# STM32H750IBK6.net
KiCad netlist of a schematic drawn in Altium Designer
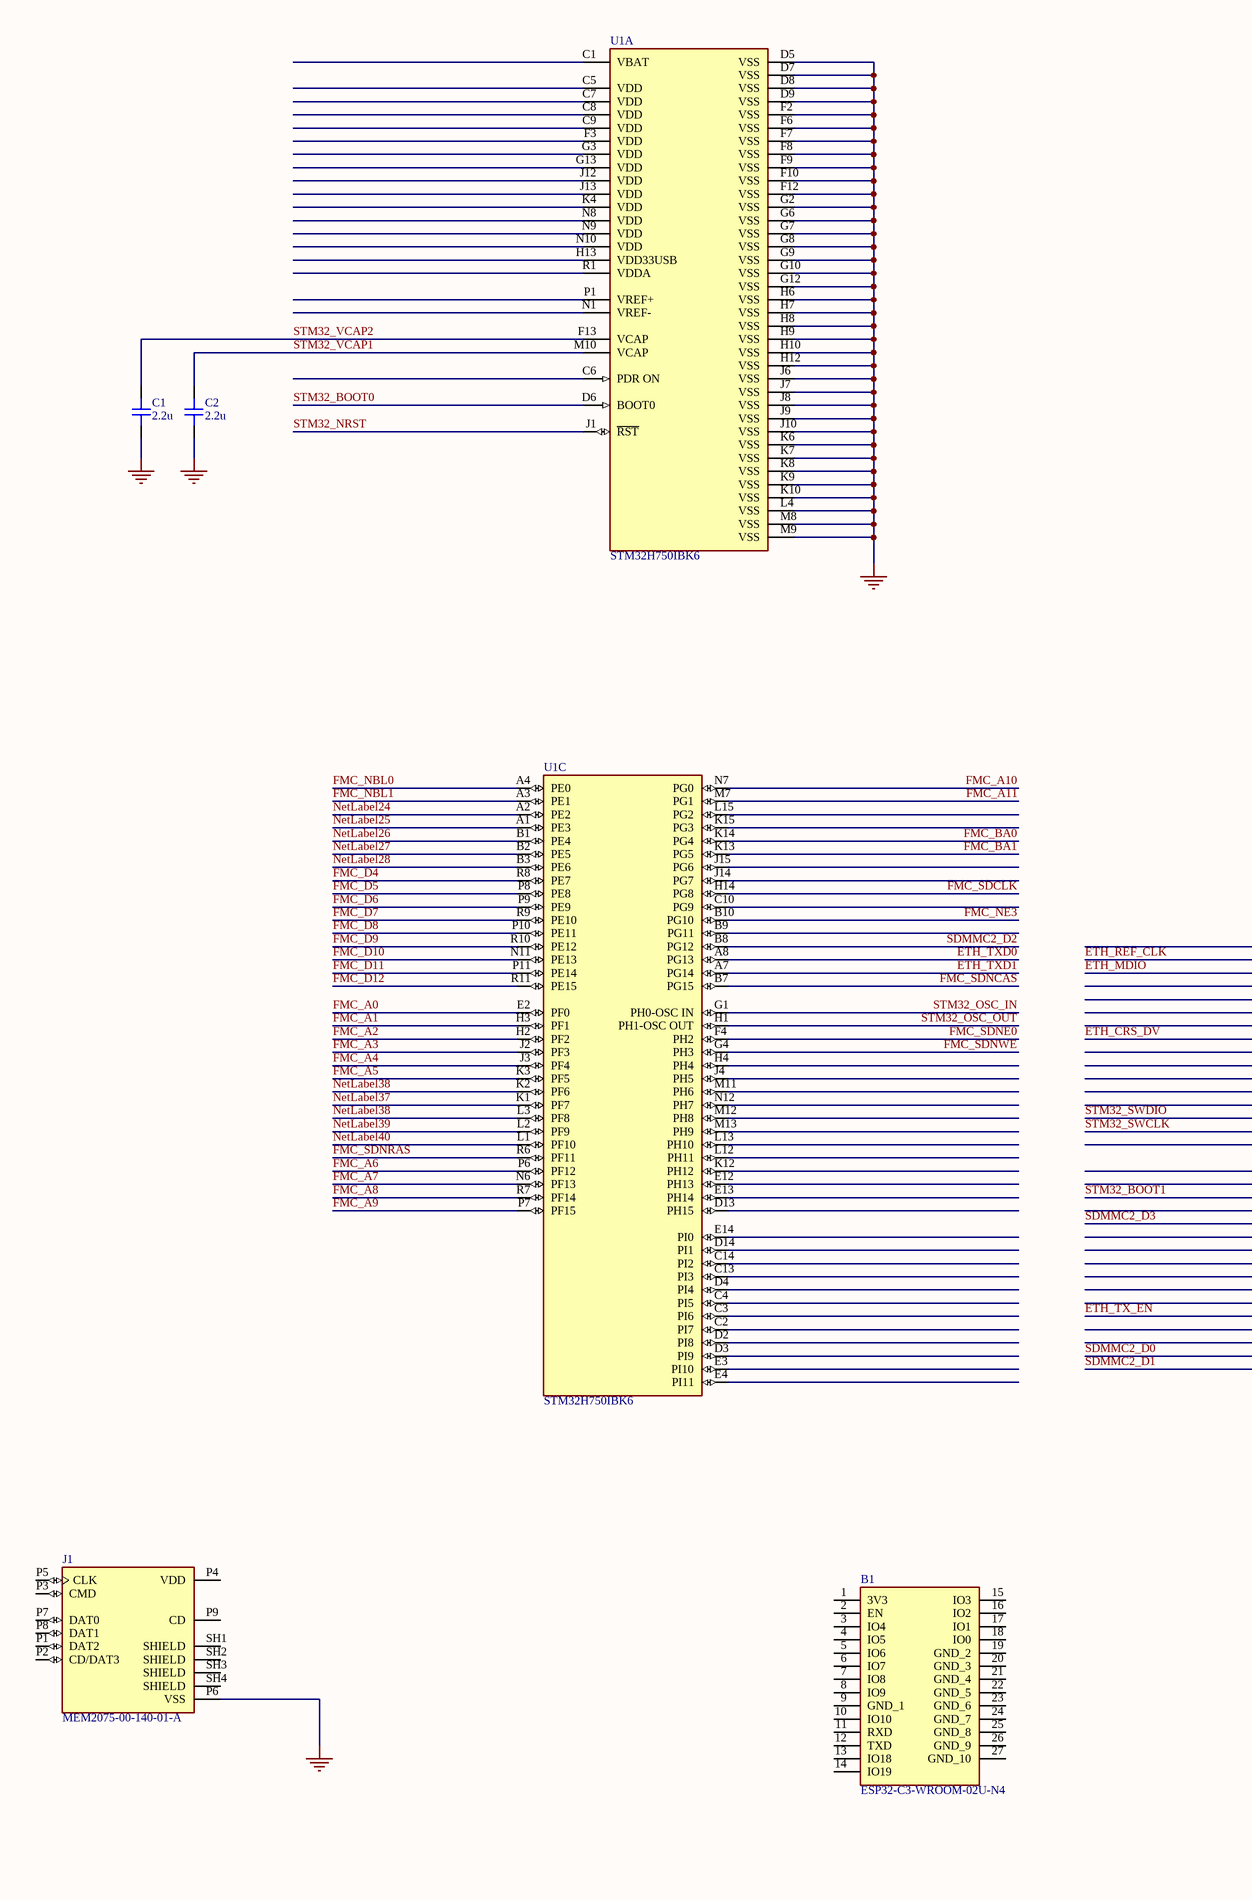
[diagram p0: STM32H750IBK6.SchDoc, left]
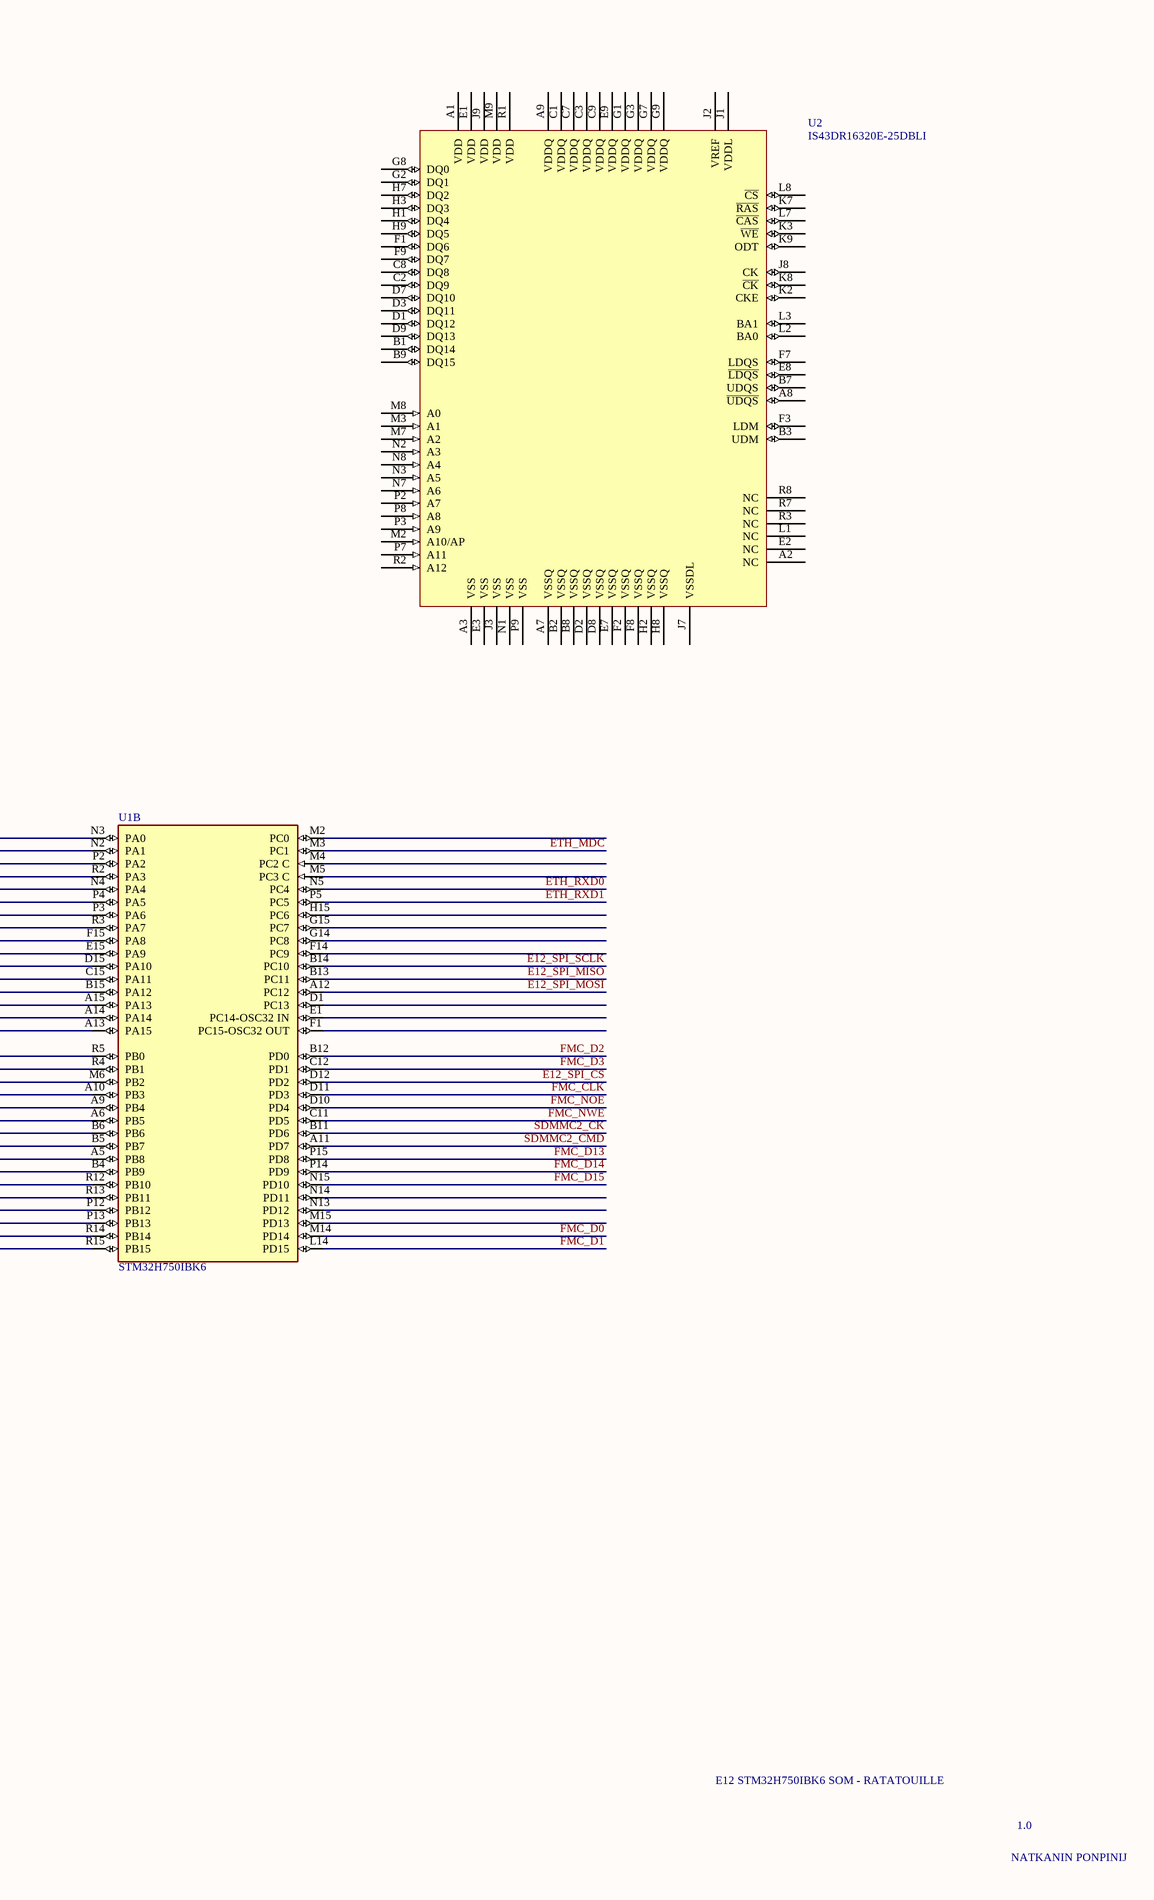
[diagram p1: STM32H750IBK6.SchDoc, right]

(export (version "E")
  (design (tool "Eeschema 10.0.6"))
  (components
    (comp (ref "B1")
      (value "ESP32-C3-WROOM-02U-N4")
      (footprint "ESP32C3WROOM02UN4")
      (description "Multiprotocol Modules SMD module, ESP32-C3, 4MB SPI flash, IPEX antenna, -40 C +85 C")
      (fields (field (name "MOUSER PART NUMBER") "356-ESP32C3WROM02UN4"))
      (libsource (lib "ESP32-C3-WROOM-02U-N4") (part "ESP32-C3-WROOM-02U-N4"))
    )
    (comp (ref "C1")
      (value "2.2u")
      (footprint "CAP_0402")
      (description "Capacitor SMD 0402 10V")
      (libsource (lib "Schematic-Lib-PhilsLab") (part "CAP_0402_10V"))
    )
    (comp (ref "C2")
      (value "2.2u")
      (footprint "CAP_0402")
      (description "Capacitor SMD 0402 10V")
      (libsource (lib "Schematic-Lib-PhilsLab") (part "CAP_0402_10V"))
    )
    (comp (ref "J1")
      (value "MEM2075-00-140-01-A")
      (footprint "GCT_MEM2075-00-140-01-A")
      (description "Micro SD Memory Card Connector, 1.4mm Profile SMT, Push-Push, with Normally open Switch")
      (libsource (lib "MEM2075-00-140-01-A") (part "MEM2075-00-140-01-A"))
    )
    (comp (ref "U1")
      (value "STM32H750IBK6")
      (footprint "FP-UFBGA176+25-A0E7-MFG")
      (description "IC MCU 32BIT 128KB FLASH 176UBGA")
      (fields
        (field (name "MANUFACTURER") "STMicroelectronics")
        (field (name "OCTOPART") "https://octopart.com/stm32h750ibk6-stmicroelectronics-94048546")
      )
      (libsource (lib "Altium Content Vault") (part "47281e30408f4b5e06a14b8d1ab2598"))
    )
    (comp (ref "U2")
      (value "IS43DR16320E-25DBLI")
      (footprint "BGA84C80P9X15_800X1250X120")
      (libsource (lib "E12WorkSpace") (part "IS43DR16320E-25DBLI-Symbol-1"))
    )
  )
  (nets
    (net (code "1") (name "/E12_SPI_CS") (class "Default")
      (node (ref "U1") (pin "D12") (pinfunction "PD2_D12") (pintype "bidirectional"))
    )
    (net (code "2") (name "/E12_SPI_MISO") (class "Default")
      (node (ref "U1") (pin "B13") (pinfunction "PC11_B13") (pintype "bidirectional"))
    )
    (net (code "3") (name "/E12_SPI_MOSI") (class "Default")
      (node (ref "U1") (pin "A12") (pinfunction "PC12_A12") (pintype "bidirectional"))
    )
    (net (code "4") (name "/E12_SPI_SCLK") (class "Default")
      (node (ref "U1") (pin "B14") (pinfunction "PC10_B14") (pintype "bidirectional"))
    )
    (net (code "5") (name "/ETH_CRS_DV") (class "Default")
      (node (ref "U1") (pin "R3") (pinfunction "PA7_R3") (pintype "bidirectional"))
    )
    (net (code "6") (name "/ETH_MDC") (class "Default")
      (node (ref "U1") (pin "M3") (pinfunction "PC1_M3") (pintype "bidirectional"))
    )
    (net (code "7") (name "/ETH_MDIO") (class "Default")
      (node (ref "U1") (pin "P2") (pinfunction "PA2_P2") (pintype "bidirectional"))
    )
    (net (code "8") (name "/ETH_REF_CLK") (class "Default")
      (node (ref "U1") (pin "N2") (pinfunction "PA1_N2") (pintype "bidirectional"))
    )
    (net (code "9") (name "/ETH_RXD0") (class "Default")
      (node (ref "U1") (pin "N5") (pinfunction "PC4_N5") (pintype "bidirectional"))
    )
    (net (code "10") (name "/ETH_RXD1") (class "Default")
      (node (ref "U1") (pin "P5") (pinfunction "PC5_P5") (pintype "bidirectional"))
    )
    (net (code "11") (name "/ETH_TXD0") (class "Default")
      (node (ref "U1") (pin "A8") (pinfunction "PG13_A8") (pintype "bidirectional"))
    )
    (net (code "12") (name "/ETH_TXD1") (class "Default")
      (node (ref "U1") (pin "A7") (pinfunction "PG14_A7") (pintype "bidirectional"))
    )
    (net (code "13") (name "/ETH_TX_EN") (class "Default")
      (node (ref "U1") (pin "R13") (pinfunction "PB11_R13") (pintype "bidirectional"))
    )
    (net (code "14") (name "/FMC_A0") (class "Default")
      (node (ref "U1") (pin "E2") (pinfunction "PF0_E2") (pintype "bidirectional"))
    )
    (net (code "15") (name "/FMC_A1") (class "Default")
      (node (ref "U1") (pin "H3") (pinfunction "PF1_H3") (pintype "bidirectional"))
    )
    (net (code "16") (name "/FMC_A2") (class "Default")
      (node (ref "U1") (pin "H2") (pinfunction "PF2_H2") (pintype "bidirectional"))
    )
    (net (code "17") (name "/FMC_A3") (class "Default")
      (node (ref "U1") (pin "J2") (pinfunction "PF3_J2") (pintype "bidirectional"))
    )
    (net (code "18") (name "/FMC_A4") (class "Default")
      (node (ref "U1") (pin "J3") (pinfunction "PF4_J3") (pintype "bidirectional"))
    )
    (net (code "19") (name "/FMC_A5") (class "Default")
      (node (ref "U1") (pin "K3") (pinfunction "PF5_K3") (pintype "bidirectional"))
    )
    (net (code "20") (name "/FMC_A6") (class "Default")
      (node (ref "U1") (pin "P6") (pinfunction "PF12_P6") (pintype "bidirectional"))
    )
    (net (code "21") (name "/FMC_A7") (class "Default")
      (node (ref "U1") (pin "N6") (pinfunction "PF13_N6") (pintype "bidirectional"))
    )
    (net (code "22") (name "/FMC_A8") (class "Default")
      (node (ref "U1") (pin "R7") (pinfunction "PF14_R7") (pintype "bidirectional"))
    )
    (net (code "23") (name "/FMC_A9") (class "Default")
      (node (ref "U1") (pin "P7") (pinfunction "PF15_P7") (pintype "bidirectional"))
    )
    (net (code "24") (name "/FMC_A10") (class "Default")
      (node (ref "U1") (pin "N7") (pinfunction "PG0_N7") (pintype "bidirectional"))
    )
    (net (code "25") (name "/FMC_A11") (class "Default")
      (node (ref "U1") (pin "M7") (pinfunction "PG1_M7") (pintype "bidirectional"))
    )
    (net (code "26") (name "/FMC_BA0") (class "Default")
      (node (ref "U1") (pin "K14") (pinfunction "PG4_K14") (pintype "bidirectional"))
    )
    (net (code "27") (name "/FMC_BA1") (class "Default")
      (node (ref "U1") (pin "K13") (pinfunction "PG5_K13") (pintype "bidirectional"))
    )
    (net (code "28") (name "/FMC_CLK") (class "Default")
      (node (ref "U1") (pin "D11") (pinfunction "PD3_D11") (pintype "bidirectional"))
    )
    (net (code "29") (name "/FMC_D0") (class "Default")
      (node (ref "U1") (pin "M14") (pinfunction "PD14_M14") (pintype "bidirectional"))
    )
    (net (code "30") (name "/FMC_D1") (class "Default")
      (node (ref "U1") (pin "L14") (pinfunction "PD15_L14") (pintype "bidirectional"))
    )
    (net (code "31") (name "/FMC_D2") (class "Default")
      (node (ref "U1") (pin "B12") (pinfunction "PD0_B12") (pintype "bidirectional"))
    )
    (net (code "32") (name "/FMC_D3") (class "Default")
      (node (ref "U1") (pin "C12") (pinfunction "PD1_C12") (pintype "bidirectional"))
    )
    (net (code "33") (name "/FMC_D4") (class "Default")
      (node (ref "U1") (pin "R8") (pinfunction "PE7_R8") (pintype "bidirectional"))
    )
    (net (code "34") (name "/FMC_D5") (class "Default")
      (node (ref "U1") (pin "P8") (pinfunction "PE8_P8") (pintype "bidirectional"))
    )
    (net (code "35") (name "/FMC_D6") (class "Default")
      (node (ref "U1") (pin "P9") (pinfunction "PE9_P9") (pintype "bidirectional"))
    )
    (net (code "36") (name "/FMC_D7") (class "Default")
      (node (ref "U1") (pin "R9") (pinfunction "PE10_R9") (pintype "bidirectional"))
    )
    (net (code "37") (name "/FMC_D8") (class "Default")
      (node (ref "U1") (pin "P10") (pinfunction "PE11_P10") (pintype "bidirectional"))
    )
    (net (code "38") (name "/FMC_D9") (class "Default")
      (node (ref "U1") (pin "R10") (pinfunction "PE12_R10") (pintype "bidirectional"))
    )
    (net (code "39") (name "/FMC_D10") (class "Default")
      (node (ref "U1") (pin "N11") (pinfunction "PE13_N11") (pintype "bidirectional"))
    )
    (net (code "40") (name "/FMC_D11") (class "Default")
      (node (ref "U1") (pin "P11") (pinfunction "PE14_P11") (pintype "bidirectional"))
    )
    (net (code "41") (name "/FMC_D12") (class "Default")
      (node (ref "U1") (pin "R11") (pinfunction "PE15_R11") (pintype "bidirectional"))
    )
    (net (code "42") (name "/FMC_D13") (class "Default")
      (node (ref "U1") (pin "P15") (pinfunction "PD8_P15") (pintype "bidirectional"))
    )
    (net (code "43") (name "/FMC_D14") (class "Default")
      (node (ref "U1") (pin "P14") (pinfunction "PD9_P14") (pintype "bidirectional"))
    )
    (net (code "44") (name "/FMC_D15") (class "Default")
      (node (ref "U1") (pin "N15") (pinfunction "PD10_N15") (pintype "bidirectional"))
    )
    (net (code "45") (name "/FMC_NBL0") (class "Default")
      (node (ref "U1") (pin "A4") (pinfunction "PE0_A4") (pintype "bidirectional"))
    )
    (net (code "46") (name "/FMC_NBL1") (class "Default")
      (node (ref "U1") (pin "A3") (pinfunction "PE1_A3") (pintype "bidirectional"))
    )
    (net (code "47") (name "/FMC_NE3") (class "Default")
      (node (ref "U1") (pin "B10") (pinfunction "PG10_B10") (pintype "bidirectional"))
    )
    (net (code "48") (name "/FMC_NOE") (class "Default")
      (node (ref "U1") (pin "D10") (pinfunction "PD4_D10") (pintype "bidirectional"))
    )
    (net (code "49") (name "/FMC_NWE") (class "Default")
      (node (ref "U1") (pin "C11") (pinfunction "PD5_C11") (pintype "bidirectional"))
    )
    (net (code "50") (name "/FMC_SDCLK") (class "Default")
      (node (ref "U1") (pin "H14") (pinfunction "PG8_H14") (pintype "bidirectional"))
    )
    (net (code "51") (name "/FMC_SDNCAS") (class "Default")
      (node (ref "U1") (pin "B7") (pinfunction "PG15_B7") (pintype "bidirectional"))
    )
    (net (code "52") (name "/FMC_SDNE0") (class "Default")
      (node (ref "U1") (pin "F4") (pinfunction "PH2_F4") (pintype "bidirectional"))
    )
    (net (code "53") (name "/FMC_SDNRAS") (class "Default")
      (node (ref "U1") (pin "R6") (pinfunction "PF11_R6") (pintype "bidirectional"))
    )
    (net (code "54") (name "/FMC_SDNWE") (class "Default")
      (node (ref "U1") (pin "G4") (pinfunction "PH3_G4") (pintype "bidirectional"))
    )
    (net (code "55") (name "/NetLabel24") (class "Default")
      (node (ref "U1") (pin "A2") (pinfunction "PE2_A2") (pintype "bidirectional"))
    )
    (net (code "56") (name "/NetLabel25") (class "Default")
      (node (ref "U1") (pin "A1") (pinfunction "PE3_A1") (pintype "bidirectional"))
    )
    (net (code "57") (name "/NetLabel26") (class "Default")
      (node (ref "U1") (pin "B1") (pinfunction "PE4_B1") (pintype "bidirectional"))
    )
    (net (code "58") (name "/NetLabel27") (class "Default")
      (node (ref "U1") (pin "B2") (pinfunction "PE5_B2") (pintype "bidirectional"))
    )
    (net (code "59") (name "/NetLabel28") (class "Default")
      (node (ref "U1") (pin "B3") (pinfunction "PE6_B3") (pintype "bidirectional"))
    )
    (net (code "60") (name "/NetLabel37") (class "Default")
      (node (ref "U1") (pin "K1") (pinfunction "PF7_K1") (pintype "bidirectional"))
    )
    (net (code "61") (name "/NetLabel38") (class "Default")
      (node (ref "U1") (pin "K2") (pinfunction "PF6_K2") (pintype "bidirectional"))
      (node (ref "U1") (pin "L3") (pinfunction "PF8_L3") (pintype "bidirectional"))
    )
    (net (code "62") (name "/NetLabel39") (class "Default")
      (node (ref "U1") (pin "L2") (pinfunction "PF9_L2") (pintype "bidirectional"))
    )
    (net (code "63") (name "/NetLabel40") (class "Default")
      (node (ref "U1") (pin "L1") (pinfunction "PF10_L1") (pintype "bidirectional"))
    )
    (net (code "64") (name "/SDMMC2_CK") (class "Default")
      (node (ref "U1") (pin "B11") (pinfunction "PD6_B11") (pintype "bidirectional"))
    )
    (net (code "65") (name "/SDMMC2_CMD") (class "Default")
      (node (ref "U1") (pin "A11") (pinfunction "PD7_A11") (pintype "bidirectional"))
    )
    (net (code "66") (name "/SDMMC2_D0") (class "Default")
      (node (ref "U1") (pin "R14") (pinfunction "PB14_R14") (pintype "bidirectional"))
    )
    (net (code "67") (name "/SDMMC2_D1") (class "Default")
      (node (ref "U1") (pin "R15") (pinfunction "PB15_R15") (pintype "bidirectional"))
    )
    (net (code "68") (name "/SDMMC2_D2") (class "Default")
      (node (ref "U1") (pin "B8") (pinfunction "PG12_B8") (pintype "bidirectional"))
    )
    (net (code "69") (name "/SDMMC2_D3") (class "Default")
      (node (ref "U1") (pin "A9") (pinfunction "PB4_A9") (pintype "bidirectional"))
    )
    (net (code "70") (name "/STM32_BOOT0") (class "Default")
      (node (ref "U1") (pin "D6") (pinfunction "BOOT0_D6") (pintype "input"))
    )
    (net (code "71") (name "/STM32_BOOT1") (class "Default")
      (node (ref "U1") (pin "M6") (pinfunction "PB2_M6") (pintype "bidirectional"))
    )
    (net (code "72") (name "/STM32_NRST") (class "Default")
      (node (ref "U1") (pin "J1") (pinfunction "~{RST}_J1") (pintype "bidirectional"))
    )
    (net (code "73") (name "/STM32_OSC_IN") (class "Default")
      (node (ref "U1") (pin "G1") (pinfunction "PH0-OSC_IN_G1") (pintype "bidirectional"))
    )
    (net (code "74") (name "/STM32_OSC_OUT") (class "Default")
      (node (ref "U1") (pin "H1") (pinfunction "PH1-OSC_OUT_H1") (pintype "bidirectional"))
    )
    (net (code "75") (name "/STM32_SWCLK") (class "Default")
      (node (ref "U1") (pin "A14") (pinfunction "PA14_A14") (pintype "bidirectional"))
    )
    (net (code "76") (name "/STM32_SWDIO") (class "Default")
      (node (ref "U1") (pin "A15") (pinfunction "PA13_A15") (pintype "bidirectional"))
    )
    (net (code "77") (name "/STM32_VCAP1") (class "Default")
      (node (ref "C2") (pin "2") (pinfunction "2_2") (pintype "passive"))
      (node (ref "U1") (pin "M10") (pinfunction "VCAP_M10") (pintype "power_in"))
    )
    (net (code "78") (name "/STM32_VCAP2") (class "Default")
      (node (ref "C1") (pin "2") (pinfunction "2_2") (pintype "passive"))
      (node (ref "U1") (pin "F13") (pinfunction "VCAP_F13") (pintype "power_in"))
    )
    (net (code "79") (name "GND") (class "Default")
      (node (ref "C1") (pin "1") (pinfunction "1_1") (pintype "passive"))
      (node (ref "C2") (pin "1") (pinfunction "1_1") (pintype "passive"))
      (node (ref "J1") (pin "P6") (pinfunction "VSS_P6") (pintype "power_in"))
      (node (ref "U1") (pin "D5") (pinfunction "VSS_D5") (pintype "power_in"))
      (node (ref "U1") (pin "D7") (pinfunction "VSS_D7") (pintype "power_in"))
      (node (ref "U1") (pin "D8") (pinfunction "VSS_D8") (pintype "power_in"))
      (node (ref "U1") (pin "D9") (pinfunction "VSS_D9") (pintype "power_in"))
      (node (ref "U1") (pin "F10") (pinfunction "VSS_F10") (pintype "power_in"))
      (node (ref "U1") (pin "F12") (pinfunction "VSS_F12") (pintype "power_in"))
      (node (ref "U1") (pin "F2") (pinfunction "VSS_F2") (pintype "power_in"))
      (node (ref "U1") (pin "F6") (pinfunction "VSS_F6") (pintype "power_in"))
      (node (ref "U1") (pin "F7") (pinfunction "VSS_F7") (pintype "power_in"))
      (node (ref "U1") (pin "F8") (pinfunction "VSS_F8") (pintype "power_in"))
      (node (ref "U1") (pin "F9") (pinfunction "VSS_F9") (pintype "power_in"))
      (node (ref "U1") (pin "G10") (pinfunction "VSS_G10") (pintype "power_in"))
      (node (ref "U1") (pin "G12") (pinfunction "VSS_G12") (pintype "power_in"))
      (node (ref "U1") (pin "G2") (pinfunction "VSS_G2") (pintype "power_in"))
      (node (ref "U1") (pin "G6") (pinfunction "VSS_G6") (pintype "power_in"))
      (node (ref "U1") (pin "G7") (pinfunction "VSS_G7") (pintype "power_in"))
      (node (ref "U1") (pin "G8") (pinfunction "VSS_G8") (pintype "power_in"))
      (node (ref "U1") (pin "G9") (pinfunction "VSS_G9") (pintype "power_in"))
      (node (ref "U1") (pin "H10") (pinfunction "VSS_H10") (pintype "power_in"))
      (node (ref "U1") (pin "H12") (pinfunction "VSS_H12") (pintype "power_in"))
      (node (ref "U1") (pin "H6") (pinfunction "VSS_H6") (pintype "power_in"))
      (node (ref "U1") (pin "H7") (pinfunction "VSS_H7") (pintype "power_in"))
      (node (ref "U1") (pin "H8") (pinfunction "VSS_H8") (pintype "power_in"))
      (node (ref "U1") (pin "H9") (pinfunction "VSS_H9") (pintype "power_in"))
      (node (ref "U1") (pin "J10") (pinfunction "VSS_J10") (pintype "power_in"))
      (node (ref "U1") (pin "J6") (pinfunction "VSS_J6") (pintype "power_in"))
      (node (ref "U1") (pin "J7") (pinfunction "VSS_J7") (pintype "power_in"))
      (node (ref "U1") (pin "J8") (pinfunction "VSS_J8") (pintype "power_in"))
      (node (ref "U1") (pin "J9") (pinfunction "VSS_J9") (pintype "power_in"))
      (node (ref "U1") (pin "K10") (pinfunction "VSS_K10") (pintype "power_in"))
      (node (ref "U1") (pin "K6") (pinfunction "VSS_K6") (pintype "power_in"))
      (node (ref "U1") (pin "K7") (pinfunction "VSS_K7") (pintype "power_in"))
      (node (ref "U1") (pin "K8") (pinfunction "VSS_K8") (pintype "power_in"))
      (node (ref "U1") (pin "K9") (pinfunction "VSS_K9") (pintype "power_in"))
      (node (ref "U1") (pin "L4") (pinfunction "VSS_L4") (pintype "power_in"))
      (node (ref "U1") (pin "M8") (pinfunction "VSS_M8") (pintype "power_in"))
      (node (ref "U1") (pin "M9") (pinfunction "VSS_M9") (pintype "power_in"))
    )
    (net (code "80") (name "unconnected-(B1-3V3-Pad1)") (class "Default")
      (node (ref "B1") (pin "1") (pinfunction "3V3_1") (pintype "passive"))
    )
    (net (code "81") (name "unconnected-(B1-EN-Pad2)") (class "Default")
      (node (ref "B1") (pin "2") (pinfunction "EN_2") (pintype "passive"))
    )
    (net (code "82") (name "unconnected-(B1-GND_1-Pad9)") (class "Default")
      (node (ref "B1") (pin "9") (pinfunction "GND_1_9") (pintype "passive"))
    )
    (net (code "83") (name "unconnected-(B1-GND_2-Pad19)") (class "Default")
      (node (ref "B1") (pin "19") (pinfunction "GND_2_19") (pintype "passive"))
    )
    (net (code "84") (name "unconnected-(B1-GND_3-Pad20)") (class "Default")
      (node (ref "B1") (pin "20") (pinfunction "GND_3_20") (pintype "passive"))
    )
    (net (code "85") (name "unconnected-(B1-GND_4-Pad21)") (class "Default")
      (node (ref "B1") (pin "21") (pinfunction "GND_4_21") (pintype "passive"))
    )
    (net (code "86") (name "unconnected-(B1-GND_5-Pad22)") (class "Default")
      (node (ref "B1") (pin "22") (pinfunction "GND_5_22") (pintype "passive"))
    )
    (net (code "87") (name "unconnected-(B1-GND_6-Pad23)") (class "Default")
      (node (ref "B1") (pin "23") (pinfunction "GND_6_23") (pintype "passive"))
    )
    (net (code "88") (name "unconnected-(B1-GND_7-Pad24)") (class "Default")
      (node (ref "B1") (pin "24") (pinfunction "GND_7_24") (pintype "passive"))
    )
    (net (code "89") (name "unconnected-(B1-GND_8-Pad25)") (class "Default")
      (node (ref "B1") (pin "25") (pinfunction "GND_8_25") (pintype "passive"))
    )
    (net (code "90") (name "unconnected-(B1-GND_9-Pad26)") (class "Default")
      (node (ref "B1") (pin "26") (pinfunction "GND_9_26") (pintype "passive"))
    )
    (net (code "91") (name "unconnected-(B1-GND_10-Pad27)") (class "Default")
      (node (ref "B1") (pin "27") (pinfunction "GND_10_27") (pintype "passive"))
    )
    (net (code "92") (name "unconnected-(B1-IO0-Pad18)") (class "Default")
      (node (ref "B1") (pin "18") (pinfunction "IO0_18") (pintype "passive"))
    )
    (net (code "93") (name "unconnected-(B1-IO1-Pad17)") (class "Default")
      (node (ref "B1") (pin "17") (pinfunction "IO1_17") (pintype "passive"))
    )
    (net (code "94") (name "unconnected-(B1-IO2-Pad16)") (class "Default")
      (node (ref "B1") (pin "16") (pinfunction "IO2_16") (pintype "passive"))
    )
    (net (code "95") (name "unconnected-(B1-IO3-Pad15)") (class "Default")
      (node (ref "B1") (pin "15") (pinfunction "IO3_15") (pintype "passive"))
    )
    (net (code "96") (name "unconnected-(B1-IO4-Pad3)") (class "Default")
      (node (ref "B1") (pin "3") (pinfunction "IO4_3") (pintype "passive"))
    )
    (net (code "97") (name "unconnected-(B1-IO5-Pad4)") (class "Default")
      (node (ref "B1") (pin "4") (pinfunction "IO5_4") (pintype "passive"))
    )
    (net (code "98") (name "unconnected-(B1-IO6-Pad5)") (class "Default")
      (node (ref "B1") (pin "5") (pinfunction "IO6_5") (pintype "passive"))
    )
    (net (code "99") (name "unconnected-(B1-IO7-Pad6)") (class "Default")
      (node (ref "B1") (pin "6") (pinfunction "IO7_6") (pintype "passive"))
    )
    (net (code "100") (name "unconnected-(B1-IO8-Pad7)") (class "Default")
      (node (ref "B1") (pin "7") (pinfunction "IO8_7") (pintype "passive"))
    )
    (net (code "101") (name "unconnected-(B1-IO9-Pad8)") (class "Default")
      (node (ref "B1") (pin "8") (pinfunction "IO9_8") (pintype "passive"))
    )
    (net (code "102") (name "unconnected-(B1-IO10-Pad10)") (class "Default")
      (node (ref "B1") (pin "10") (pinfunction "IO10_10") (pintype "passive"))
    )
    (net (code "103") (name "unconnected-(B1-IO18-Pad13)") (class "Default")
      (node (ref "B1") (pin "13") (pinfunction "IO18_13") (pintype "passive"))
    )
    (net (code "104") (name "unconnected-(B1-IO19-Pad14)") (class "Default")
      (node (ref "B1") (pin "14") (pinfunction "IO19_14") (pintype "passive"))
    )
    (net (code "105") (name "unconnected-(B1-RXD-Pad11)") (class "Default")
      (node (ref "B1") (pin "11") (pinfunction "RXD_11") (pintype "passive"))
    )
    (net (code "106") (name "unconnected-(B1-TXD-Pad12)") (class "Default")
      (node (ref "B1") (pin "12") (pinfunction "TXD_12") (pintype "passive"))
    )
    (net (code "107") (name "unconnected-(J1-CD-PadP9)") (class "Default")
      (node (ref "J1") (pin "P9") (pinfunction "CD_P9") (pintype "passive"))
    )
    (net (code "108") (name "unconnected-(J1-CD{slash}DAT3-PadP2)") (class "Default")
      (node (ref "J1") (pin "P2") (pinfunction "CD/DAT3_P2") (pintype "bidirectional"))
    )
    (net (code "109") (name "unconnected-(J1-CLK-PadP5)") (class "Default")
      (node (ref "J1") (pin "P5") (pinfunction "CLK_P5") (pintype "bidirectional"))
    )
    (net (code "110") (name "unconnected-(J1-CMD-PadP3)") (class "Default")
      (node (ref "J1") (pin "P3") (pinfunction "CMD_P3") (pintype "bidirectional"))
    )
    (net (code "111") (name "unconnected-(J1-DAT0-PadP7)") (class "Default")
      (node (ref "J1") (pin "P7") (pinfunction "DAT0_P7") (pintype "bidirectional"))
    )
    (net (code "112") (name "unconnected-(J1-DAT1-PadP8)") (class "Default")
      (node (ref "J1") (pin "P8") (pinfunction "DAT1_P8") (pintype "bidirectional"))
    )
    (net (code "113") (name "unconnected-(J1-DAT2-PadP1)") (class "Default")
      (node (ref "J1") (pin "P1") (pinfunction "DAT2_P1") (pintype "bidirectional"))
    )
    (net (code "114") (name "unconnected-(J1-SHIELD-PadSH1)") (class "Default")
      (node (ref "J1") (pin "SH1") (pinfunction "SHIELD_SH1") (pintype "power_in"))
    )
    (net (code "115") (name "unconnected-(J1-SHIELD-PadSH2)") (class "Default")
      (node (ref "J1") (pin "SH2") (pinfunction "SHIELD_SH2") (pintype "power_in"))
    )
    (net (code "116") (name "unconnected-(J1-SHIELD-PadSH3)") (class "Default")
      (node (ref "J1") (pin "SH3") (pinfunction "SHIELD_SH3") (pintype "power_in"))
    )
    (net (code "117") (name "unconnected-(J1-SHIELD-PadSH4)") (class "Default")
      (node (ref "J1") (pin "SH4") (pinfunction "SHIELD_SH4") (pintype "power_in"))
    )
    (net (code "118") (name "unconnected-(J1-VDD-PadP4)") (class "Default")
      (node (ref "J1") (pin "P4") (pinfunction "VDD_P4") (pintype "power_in"))
    )
    (net (code "119") (name "unconnected-(U1A-PDR_ON-PadC6)") (class "Default")
      (node (ref "U1") (pin "C6") (pinfunction "PDR_ON_C6") (pintype "input"))
    )
    (net (code "120") (name "unconnected-(U1A-VBAT-PadC1)") (class "Default")
      (node (ref "U1") (pin "C1") (pinfunction "VBAT_C1") (pintype "power_in"))
    )
    (net (code "121") (name "unconnected-(U1A-VDD-PadC5)") (class "Default")
      (node (ref "U1") (pin "C5") (pinfunction "VDD_C5") (pintype "power_in"))
    )
    (net (code "122") (name "unconnected-(U1A-VDD-PadC7)") (class "Default")
      (node (ref "U1") (pin "C7") (pinfunction "VDD_C7") (pintype "power_in"))
    )
    (net (code "123") (name "unconnected-(U1A-VDD-PadC8)") (class "Default")
      (node (ref "U1") (pin "C8") (pinfunction "VDD_C8") (pintype "power_in"))
    )
    (net (code "124") (name "unconnected-(U1A-VDD-PadC9)") (class "Default")
      (node (ref "U1") (pin "C9") (pinfunction "VDD_C9") (pintype "power_in"))
    )
    (net (code "125") (name "unconnected-(U1A-VDD-PadF3)") (class "Default")
      (node (ref "U1") (pin "F3") (pinfunction "VDD_F3") (pintype "power_in"))
    )
    (net (code "126") (name "unconnected-(U1A-VDD-PadG3)") (class "Default")
      (node (ref "U1") (pin "G3") (pinfunction "VDD_G3") (pintype "power_in"))
    )
    (net (code "127") (name "unconnected-(U1A-VDD-PadG13)") (class "Default")
      (node (ref "U1") (pin "G13") (pinfunction "VDD_G13") (pintype "power_in"))
    )
    (net (code "128") (name "unconnected-(U1A-VDD-PadJ12)") (class "Default")
      (node (ref "U1") (pin "J12") (pinfunction "VDD_J12") (pintype "power_in"))
    )
    (net (code "129") (name "unconnected-(U1A-VDD-PadJ13)") (class "Default")
      (node (ref "U1") (pin "J13") (pinfunction "VDD_J13") (pintype "power_in"))
    )
    (net (code "130") (name "unconnected-(U1A-VDD-PadK4)") (class "Default")
      (node (ref "U1") (pin "K4") (pinfunction "VDD_K4") (pintype "power_in"))
    )
    (net (code "131") (name "unconnected-(U1A-VDD-PadN8)") (class "Default")
      (node (ref "U1") (pin "N8") (pinfunction "VDD_N8") (pintype "power_in"))
    )
    (net (code "132") (name "unconnected-(U1A-VDD-PadN9)") (class "Default")
      (node (ref "U1") (pin "N9") (pinfunction "VDD_N9") (pintype "power_in"))
    )
    (net (code "133") (name "unconnected-(U1A-VDD-PadN10)") (class "Default")
      (node (ref "U1") (pin "N10") (pinfunction "VDD_N10") (pintype "power_in"))
    )
    (net (code "134") (name "unconnected-(U1A-VDD33USB-PadH13)") (class "Default")
      (node (ref "U1") (pin "H13") (pinfunction "VDD33USB_H13") (pintype "power_in"))
    )
    (net (code "135") (name "unconnected-(U1A-VDDA-PadR1)") (class "Default")
      (node (ref "U1") (pin "R1") (pinfunction "VDDA_R1") (pintype "power_in"))
    )
    (net (code "136") (name "unconnected-(U1A-VREF+-PadP1)") (class "Default")
      (node (ref "U1") (pin "P1") (pinfunction "VREF+_P1") (pintype "power_in"))
    )
    (net (code "137") (name "unconnected-(U1A-VREF--PadN1)") (class "Default")
      (node (ref "U1") (pin "N1") (pinfunction "VREF-_N1") (pintype "power_in"))
    )
    (net (code "138") (name "unconnected-(U1B-PA0-PadN3)") (class "Default")
      (node (ref "U1") (pin "N3") (pinfunction "PA0_N3") (pintype "bidirectional"))
    )
    (net (code "139") (name "unconnected-(U1B-PA3-PadR2)") (class "Default")
      (node (ref "U1") (pin "R2") (pinfunction "PA3_R2") (pintype "bidirectional"))
    )
    (net (code "140") (name "unconnected-(U1B-PA4-PadN4)") (class "Default")
      (node (ref "U1") (pin "N4") (pinfunction "PA4_N4") (pintype "bidirectional"))
    )
    (net (code "141") (name "unconnected-(U1B-PA5-PadP4)") (class "Default")
      (node (ref "U1") (pin "P4") (pinfunction "PA5_P4") (pintype "bidirectional"))
    )
    (net (code "142") (name "unconnected-(U1B-PA6-PadP3)") (class "Default")
      (node (ref "U1") (pin "P3") (pinfunction "PA6_P3") (pintype "bidirectional"))
    )
    (net (code "143") (name "unconnected-(U1B-PA8-PadF15)") (class "Default")
      (node (ref "U1") (pin "F15") (pinfunction "PA8_F15") (pintype "bidirectional"))
    )
    (net (code "144") (name "unconnected-(U1B-PA9-PadE15)") (class "Default")
      (node (ref "U1") (pin "E15") (pinfunction "PA9_E15") (pintype "bidirectional"))
    )
    (net (code "145") (name "unconnected-(U1B-PA10-PadD15)") (class "Default")
      (node (ref "U1") (pin "D15") (pinfunction "PA10_D15") (pintype "bidirectional"))
    )
    (net (code "146") (name "unconnected-(U1B-PA11-PadC15)") (class "Default")
      (node (ref "U1") (pin "C15") (pinfunction "PA11_C15") (pintype "bidirectional"))
    )
    (net (code "147") (name "unconnected-(U1B-PA12-PadB15)") (class "Default")
      (node (ref "U1") (pin "B15") (pinfunction "PA12_B15") (pintype "bidirectional"))
    )
    (net (code "148") (name "unconnected-(U1B-PA15-PadA13)") (class "Default")
      (node (ref "U1") (pin "A13") (pinfunction "PA15_A13") (pintype "bidirectional"))
    )
    (net (code "149") (name "unconnected-(U1B-PB0-PadR5)") (class "Default")
      (node (ref "U1") (pin "R5") (pinfunction "PB0_R5") (pintype "bidirectional"))
    )
    (net (code "150") (name "unconnected-(U1B-PB1-PadR4)") (class "Default")
      (node (ref "U1") (pin "R4") (pinfunction "PB1_R4") (pintype "bidirectional"))
    )
    (net (code "151") (name "unconnected-(U1B-PB3-PadA10)") (class "Default")
      (node (ref "U1") (pin "A10") (pinfunction "PB3_A10") (pintype "bidirectional"))
    )
    (net (code "152") (name "unconnected-(U1B-PB5-PadA6)") (class "Default")
      (node (ref "U1") (pin "A6") (pinfunction "PB5_A6") (pintype "bidirectional"))
    )
    (net (code "153") (name "unconnected-(U1B-PB6-PadB6)") (class "Default")
      (node (ref "U1") (pin "B6") (pinfunction "PB6_B6") (pintype "bidirectional"))
    )
    (net (code "154") (name "unconnected-(U1B-PB7-PadB5)") (class "Default")
      (node (ref "U1") (pin "B5") (pinfunction "PB7_B5") (pintype "bidirectional"))
    )
    (net (code "155") (name "unconnected-(U1B-PB8-PadA5)") (class "Default")
      (node (ref "U1") (pin "A5") (pinfunction "PB8_A5") (pintype "bidirectional"))
    )
    (net (code "156") (name "unconnected-(U1B-PB9-PadB4)") (class "Default")
      (node (ref "U1") (pin "B4") (pinfunction "PB9_B4") (pintype "bidirectional"))
    )
    (net (code "157") (name "unconnected-(U1B-PB10-PadR12)") (class "Default")
      (node (ref "U1") (pin "R12") (pinfunction "PB10_R12") (pintype "bidirectional"))
    )
    (net (code "158") (name "unconnected-(U1B-PB12-PadP12)") (class "Default")
      (node (ref "U1") (pin "P12") (pinfunction "PB12_P12") (pintype "bidirectional"))
    )
    (net (code "159") (name "unconnected-(U1B-PB13-PadP13)") (class "Default")
      (node (ref "U1") (pin "P13") (pinfunction "PB13_P13") (pintype "bidirectional"))
    )
    (net (code "160") (name "unconnected-(U1B-PC0-PadM2)") (class "Default")
      (node (ref "U1") (pin "M2") (pinfunction "PC0_M2") (pintype "bidirectional"))
    )
    (net (code "161") (name "unconnected-(U1B-PC2_C-PadM4)") (class "Default")
      (node (ref "U1") (pin "M4") (pinfunction "PC2_C_M4") (pintype "input"))
    )
    (net (code "162") (name "unconnected-(U1B-PC3_C-PadM5)") (class "Default")
      (node (ref "U1") (pin "M5") (pinfunction "PC3_C_M5") (pintype "input"))
    )
    (net (code "163") (name "unconnected-(U1B-PC6-PadH15)") (class "Default")
      (node (ref "U1") (pin "H15") (pinfunction "PC6_H15") (pintype "bidirectional"))
    )
    (net (code "164") (name "unconnected-(U1B-PC7-PadG15)") (class "Default")
      (node (ref "U1") (pin "G15") (pinfunction "PC7_G15") (pintype "bidirectional"))
    )
    (net (code "165") (name "unconnected-(U1B-PC8-PadG14)") (class "Default")
      (node (ref "U1") (pin "G14") (pinfunction "PC8_G14") (pintype "bidirectional"))
    )
    (net (code "166") (name "unconnected-(U1B-PC9-PadF14)") (class "Default")
      (node (ref "U1") (pin "F14") (pinfunction "PC9_F14") (pintype "bidirectional"))
    )
    (net (code "167") (name "unconnected-(U1B-PC13-PadD1)") (class "Default")
      (node (ref "U1") (pin "D1") (pinfunction "PC13_D1") (pintype "bidirectional"))
    )
    (net (code "168") (name "unconnected-(U1B-PC14-OSC32_IN-PadE1)") (class "Default")
      (node (ref "U1") (pin "E1") (pinfunction "PC14-OSC32_IN_E1") (pintype "bidirectional"))
    )
    (net (code "169") (name "unconnected-(U1B-PC15-OSC32_OUT-PadF1)") (class "Default")
      (node (ref "U1") (pin "F1") (pinfunction "PC15-OSC32_OUT_F1") (pintype "bidirectional"))
    )
    (net (code "170") (name "unconnected-(U1B-PD11-PadN14)") (class "Default")
      (node (ref "U1") (pin "N14") (pinfunction "PD11_N14") (pintype "bidirectional"))
    )
    (net (code "171") (name "unconnected-(U1B-PD12-PadN13)") (class "Default")
      (node (ref "U1") (pin "N13") (pinfunction "PD12_N13") (pintype "bidirectional"))
    )
    (net (code "172") (name "unconnected-(U1B-PD13-PadM15)") (class "Default")
      (node (ref "U1") (pin "M15") (pinfunction "PD13_M15") (pintype "bidirectional"))
    )
    (net (code "173") (name "unconnected-(U1C-PG2-PadL15)") (class "Default")
      (node (ref "U1") (pin "L15") (pinfunction "PG2_L15") (pintype "bidirectional"))
    )
    (net (code "174") (name "unconnected-(U1C-PG3-PadK15)") (class "Default")
      (node (ref "U1") (pin "K15") (pinfunction "PG3_K15") (pintype "bidirectional"))
    )
    (net (code "175") (name "unconnected-(U1C-PG6-PadJ15)") (class "Default")
      (node (ref "U1") (pin "J15") (pinfunction "PG6_J15") (pintype "bidirectional"))
    )
    (net (code "176") (name "unconnected-(U1C-PG7-PadJ14)") (class "Default")
      (node (ref "U1") (pin "J14") (pinfunction "PG7_J14") (pintype "bidirectional"))
    )
    (net (code "177") (name "unconnected-(U1C-PG9-PadC10)") (class "Default")
      (node (ref "U1") (pin "C10") (pinfunction "PG9_C10") (pintype "bidirectional"))
    )
    (net (code "178") (name "unconnected-(U1C-PG11-PadB9)") (class "Default")
      (node (ref "U1") (pin "B9") (pinfunction "PG11_B9") (pintype "bidirectional"))
    )
    (net (code "179") (name "unconnected-(U1C-PH4-PadH4)") (class "Default")
      (node (ref "U1") (pin "H4") (pinfunction "PH4_H4") (pintype "bidirectional"))
    )
    (net (code "180") (name "unconnected-(U1C-PH5-PadJ4)") (class "Default")
      (node (ref "U1") (pin "J4") (pinfunction "PH5_J4") (pintype "bidirectional"))
    )
    (net (code "181") (name "unconnected-(U1C-PH6-PadM11)") (class "Default")
      (node (ref "U1") (pin "M11") (pinfunction "PH6_M11") (pintype "bidirectional"))
    )
    (net (code "182") (name "unconnected-(U1C-PH7-PadN12)") (class "Default")
      (node (ref "U1") (pin "N12") (pinfunction "PH7_N12") (pintype "bidirectional"))
    )
    (net (code "183") (name "unconnected-(U1C-PH8-PadM12)") (class "Default")
      (node (ref "U1") (pin "M12") (pinfunction "PH8_M12") (pintype "bidirectional"))
    )
    (net (code "184") (name "unconnected-(U1C-PH9-PadM13)") (class "Default")
      (node (ref "U1") (pin "M13") (pinfunction "PH9_M13") (pintype "bidirectional"))
    )
    (net (code "185") (name "unconnected-(U1C-PH10-PadL13)") (class "Default")
      (node (ref "U1") (pin "L13") (pinfunction "PH10_L13") (pintype "bidirectional"))
    )
    (net (code "186") (name "unconnected-(U1C-PH11-PadL12)") (class "Default")
      (node (ref "U1") (pin "L12") (pinfunction "PH11_L12") (pintype "bidirectional"))
    )
    (net (code "187") (name "unconnected-(U1C-PH12-PadK12)") (class "Default")
      (node (ref "U1") (pin "K12") (pinfunction "PH12_K12") (pintype "bidirectional"))
    )
    (net (code "188") (name "unconnected-(U1C-PH13-PadE12)") (class "Default")
      (node (ref "U1") (pin "E12") (pinfunction "PH13_E12") (pintype "bidirectional"))
    )
    (net (code "189") (name "unconnected-(U1C-PH14-PadE13)") (class "Default")
      (node (ref "U1") (pin "E13") (pinfunction "PH14_E13") (pintype "bidirectional"))
    )
    (net (code "190") (name "unconnected-(U1C-PH15-PadD13)") (class "Default")
      (node (ref "U1") (pin "D13") (pinfunction "PH15_D13") (pintype "bidirectional"))
    )
    (net (code "191") (name "unconnected-(U1C-PI0-PadE14)") (class "Default")
      (node (ref "U1") (pin "E14") (pinfunction "PI0_E14") (pintype "bidirectional"))
    )
    (net (code "192") (name "unconnected-(U1C-PI1-PadD14)") (class "Default")
      (node (ref "U1") (pin "D14") (pinfunction "PI1_D14") (pintype "bidirectional"))
    )
    (net (code "193") (name "unconnected-(U1C-PI2-PadC14)") (class "Default")
      (node (ref "U1") (pin "C14") (pinfunction "PI2_C14") (pintype "bidirectional"))
    )
    (net (code "194") (name "unconnected-(U1C-PI3-PadC13)") (class "Default")
      (node (ref "U1") (pin "C13") (pinfunction "PI3_C13") (pintype "bidirectional"))
    )
    (net (code "195") (name "unconnected-(U1C-PI4-PadD4)") (class "Default")
      (node (ref "U1") (pin "D4") (pinfunction "PI4_D4") (pintype "bidirectional"))
    )
    (net (code "196") (name "unconnected-(U1C-PI5-PadC4)") (class "Default")
      (node (ref "U1") (pin "C4") (pinfunction "PI5_C4") (pintype "bidirectional"))
    )
    (net (code "197") (name "unconnected-(U1C-PI6-PadC3)") (class "Default")
      (node (ref "U1") (pin "C3") (pinfunction "PI6_C3") (pintype "bidirectional"))
    )
    (net (code "198") (name "unconnected-(U1C-PI7-PadC2)") (class "Default")
      (node (ref "U1") (pin "C2") (pinfunction "PI7_C2") (pintype "bidirectional"))
    )
    (net (code "199") (name "unconnected-(U1C-PI8-PadD2)") (class "Default")
      (node (ref "U1") (pin "D2") (pinfunction "PI8_D2") (pintype "bidirectional"))
    )
    (net (code "200") (name "unconnected-(U1C-PI9-PadD3)") (class "Default")
      (node (ref "U1") (pin "D3") (pinfunction "PI9_D3") (pintype "bidirectional"))
    )
    (net (code "201") (name "unconnected-(U1C-PI10-PadE3)") (class "Default")
      (node (ref "U1") (pin "E3") (pinfunction "PI10_E3") (pintype "bidirectional"))
    )
    (net (code "202") (name "unconnected-(U1C-PI11-PadE4)") (class "Default")
      (node (ref "U1") (pin "E4") (pinfunction "PI11_E4") (pintype "bidirectional"))
    )
    (net (code "203") (name "unconnected-(U2-A0-PadM8)") (class "Default")
      (node (ref "U2") (pin "M8") (pinfunction "A0_M8") (pintype "input"))
    )
    (net (code "204") (name "unconnected-(U2-A1-PadM3)") (class "Default")
      (node (ref "U2") (pin "M3") (pinfunction "A1_M3") (pintype "input"))
    )
    (net (code "205") (name "unconnected-(U2-A2-PadM7)") (class "Default")
      (node (ref "U2") (pin "M7") (pinfunction "A2_M7") (pintype "input"))
    )
    (net (code "206") (name "unconnected-(U2-A3-PadN2)") (class "Default")
      (node (ref "U2") (pin "N2") (pinfunction "A3_N2") (pintype "input"))
    )
    (net (code "207") (name "unconnected-(U2-A4-PadN8)") (class "Default")
      (node (ref "U2") (pin "N8") (pinfunction "A4_N8") (pintype "input"))
    )
    (net (code "208") (name "unconnected-(U2-A5-PadN3)") (class "Default")
      (node (ref "U2") (pin "N3") (pinfunction "A5_N3") (pintype "input"))
    )
    (net (code "209") (name "unconnected-(U2-A6-PadN7)") (class "Default")
      (node (ref "U2") (pin "N7") (pinfunction "A6_N7") (pintype "input"))
    )
    (net (code "210") (name "unconnected-(U2-A7-PadP2)") (class "Default")
      (node (ref "U2") (pin "P2") (pinfunction "A7_P2") (pintype "input"))
    )
    (net (code "211") (name "unconnected-(U2-A8-PadP8)") (class "Default")
      (node (ref "U2") (pin "P8") (pinfunction "A8_P8") (pintype "input"))
    )
    (net (code "212") (name "unconnected-(U2-A9-PadP3)") (class "Default")
      (node (ref "U2") (pin "P3") (pinfunction "A9_P3") (pintype "input"))
    )
    (net (code "213") (name "unconnected-(U2-A10{slash}AP-PadM2)") (class "Default")
      (node (ref "U2") (pin "M2") (pinfunction "A10/AP_M2") (pintype "input"))
    )
    (net (code "214") (name "unconnected-(U2-A11-PadP7)") (class "Default")
      (node (ref "U2") (pin "P7") (pinfunction "A11_P7") (pintype "input"))
    )
    (net (code "215") (name "unconnected-(U2-A12-PadR2)") (class "Default")
      (node (ref "U2") (pin "R2") (pinfunction "A12_R2") (pintype "input"))
    )
    (net (code "216") (name "unconnected-(U2-BA0-PadL2)") (class "Default")
      (node (ref "U2") (pin "L2") (pinfunction "BA0_L2") (pintype "bidirectional"))
    )
    (net (code "217") (name "unconnected-(U2-BA1-PadL3)") (class "Default")
      (node (ref "U2") (pin "L3") (pinfunction "BA1_L3") (pintype "bidirectional"))
    )
    (net (code "218") (name "unconnected-(U2-CK-PadJ8)") (class "Default")
      (node (ref "U2") (pin "J8") (pinfunction "CK_J8") (pintype "bidirectional"))
    )
    (net (code "219") (name "unconnected-(U2-CKE-PadK2)") (class "Default")
      (node (ref "U2") (pin "K2") (pinfunction "CKE_K2") (pintype "bidirectional"))
    )
    (net (code "220") (name "unconnected-(U2-DQ0-PadG8)") (class "Default")
      (node (ref "U2") (pin "G8") (pinfunction "DQ0_G8") (pintype "bidirectional"))
    )
    (net (code "221") (name "unconnected-(U2-DQ1-PadG2)") (class "Default")
      (node (ref "U2") (pin "G2") (pinfunction "DQ1_G2") (pintype "bidirectional"))
    )
    (net (code "222") (name "unconnected-(U2-DQ2-PadH7)") (class "Default")
      (node (ref "U2") (pin "H7") (pinfunction "DQ2_H7") (pintype "bidirectional"))
    )
    (net (code "223") (name "unconnected-(U2-DQ3-PadH3)") (class "Default")
      (node (ref "U2") (pin "H3") (pinfunction "DQ3_H3") (pintype "bidirectional"))
    )
    (net (code "224") (name "unconnected-(U2-DQ4-PadH1)") (class "Default")
      (node (ref "U2") (pin "H1") (pinfunction "DQ4_H1") (pintype "bidirectional"))
    )
    (net (code "225") (name "unconnected-(U2-DQ5-PadH9)") (class "Default")
      (node (ref "U2") (pin "H9") (pinfunction "DQ5_H9") (pintype "bidirectional"))
    )
    (net (code "226") (name "unconnected-(U2-DQ6-PadF1)") (class "Default")
      (node (ref "U2") (pin "F1") (pinfunction "DQ6_F1") (pintype "bidirectional"))
    )
    (net (code "227") (name "unconnected-(U2-DQ7-PadF9)") (class "Default")
      (node (ref "U2") (pin "F9") (pinfunction "DQ7_F9") (pintype "bidirectional"))
    )
    (net (code "228") (name "unconnected-(U2-DQ8-PadC8)") (class "Default")
      (node (ref "U2") (pin "C8") (pinfunction "DQ8_C8") (pintype "bidirectional"))
    )
    (net (code "229") (name "unconnected-(U2-DQ9-PadC2)") (class "Default")
      (node (ref "U2") (pin "C2") (pinfunction "DQ9_C2") (pintype "bidirectional"))
    )
    (net (code "230") (name "unconnected-(U2-DQ10-PadD7)") (class "Default")
      (node (ref "U2") (pin "D7") (pinfunction "DQ10_D7") (pintype "bidirectional"))
    )
    (net (code "231") (name "unconnected-(U2-DQ11-PadD3)") (class "Default")
      (node (ref "U2") (pin "D3") (pinfunction "DQ11_D3") (pintype "bidirectional"))
    )
    (net (code "232") (name "unconnected-(U2-DQ12-PadD1)") (class "Default")
      (node (ref "U2") (pin "D1") (pinfunction "DQ12_D1") (pintype "bidirectional"))
    )
    (net (code "233") (name "unconnected-(U2-DQ13-PadD9)") (class "Default")
      (node (ref "U2") (pin "D9") (pinfunction "DQ13_D9") (pintype "bidirectional"))
    )
    (net (code "234") (name "unconnected-(U2-DQ14-PadB1)") (class "Default")
      (node (ref "U2") (pin "B1") (pinfunction "DQ14_B1") (pintype "bidirectional"))
    )
    (net (code "235") (name "unconnected-(U2-DQ15-PadB9)") (class "Default")
      (node (ref "U2") (pin "B9") (pinfunction "DQ15_B9") (pintype "bidirectional"))
    )
    (net (code "236") (name "unconnected-(U2-LDM-PadF3)") (class "Default")
      (node (ref "U2") (pin "F3") (pinfunction "LDM_F3") (pintype "bidirectional"))
    )
    (net (code "237") (name "unconnected-(U2-LDQS-PadF7)") (class "Default")
      (node (ref "U2") (pin "F7") (pinfunction "LDQS_F7") (pintype "bidirectional"))
    )
    (net (code "238") (name "unconnected-(U2-NC-PadA2)") (class "Default")
      (node (ref "U2") (pin "A2") (pinfunction "NC_A2") (pintype "passive"))
    )
    (net (code "239") (name "unconnected-(U2-NC-PadE2)") (class "Default")
      (node (ref "U2") (pin "E2") (pinfunction "NC_E2") (pintype "passive"))
    )
    (net (code "240") (name "unconnected-(U2-NC-PadL1)") (class "Default")
      (node (ref "U2") (pin "L1") (pinfunction "NC_L1") (pintype "passive"))
    )
    (net (code "241") (name "unconnected-(U2-NC-PadR3)") (class "Default")
      (node (ref "U2") (pin "R3") (pinfunction "NC_R3") (pintype "passive"))
    )
    (net (code "242") (name "unconnected-(U2-NC-PadR7)") (class "Default")
      (node (ref "U2") (pin "R7") (pinfunction "NC_R7") (pintype "passive"))
    )
    (net (code "243") (name "unconnected-(U2-NC-PadR8)") (class "Default")
      (node (ref "U2") (pin "R8") (pinfunction "NC_R8") (pintype "passive"))
    )
    (net (code "244") (name "unconnected-(U2-ODT-PadK9)") (class "Default")
      (node (ref "U2") (pin "K9") (pinfunction "ODT_K9") (pintype "bidirectional"))
    )
    (net (code "245") (name "unconnected-(U2-UDM-PadB3)") (class "Default")
      (node (ref "U2") (pin "B3") (pinfunction "UDM_B3") (pintype "bidirectional"))
    )
    (net (code "246") (name "unconnected-(U2-UDQS-PadB7)") (class "Default")
      (node (ref "U2") (pin "B7") (pinfunction "UDQS_B7") (pintype "bidirectional"))
    )
    (net (code "247") (name "unconnected-(U2-VDD-PadA1)") (class "Default")
      (node (ref "U2") (pin "A1") (pinfunction "VDD_A1") (pintype "power_in"))
    )
    (net (code "248") (name "unconnected-(U2-VDD-PadE1)") (class "Default")
      (node (ref "U2") (pin "E1") (pinfunction "VDD_E1") (pintype "power_in"))
    )
    (net (code "249") (name "unconnected-(U2-VDD-PadJ9)") (class "Default")
      (node (ref "U2") (pin "J9") (pinfunction "VDD_J9") (pintype "power_in"))
    )
    (net (code "250") (name "unconnected-(U2-VDD-PadM9)") (class "Default")
      (node (ref "U2") (pin "M9") (pinfunction "VDD_M9") (pintype "power_in"))
    )
    (net (code "251") (name "unconnected-(U2-VDD-PadR1)") (class "Default")
      (node (ref "U2") (pin "R1") (pinfunction "VDD_R1") (pintype "power_in"))
    )
    (net (code "252") (name "unconnected-(U2-VDDL-PadJ1)") (class "Default")
      (node (ref "U2") (pin "J1") (pinfunction "VDDL_J1") (pintype "power_in"))
    )
    (net (code "253") (name "unconnected-(U2-VDDQ-PadA9)") (class "Default")
      (node (ref "U2") (pin "A9") (pinfunction "VDDQ_A9") (pintype "power_in"))
    )
    (net (code "254") (name "unconnected-(U2-VDDQ-PadC1)") (class "Default")
      (node (ref "U2") (pin "C1") (pinfunction "VDDQ_C1") (pintype "power_in"))
    )
    (net (code "255") (name "unconnected-(U2-VDDQ-PadC3)") (class "Default")
      (node (ref "U2") (pin "C3") (pinfunction "VDDQ_C3") (pintype "power_in"))
    )
    (net (code "256") (name "unconnected-(U2-VDDQ-PadC7)") (class "Default")
      (node (ref "U2") (pin "C7") (pinfunction "VDDQ_C7") (pintype "power_in"))
    )
    (net (code "257") (name "unconnected-(U2-VDDQ-PadC9)") (class "Default")
      (node (ref "U2") (pin "C9") (pinfunction "VDDQ_C9") (pintype "power_in"))
    )
    (net (code "258") (name "unconnected-(U2-VDDQ-PadE9)") (class "Default")
      (node (ref "U2") (pin "E9") (pinfunction "VDDQ_E9") (pintype "power_in"))
    )
    (net (code "259") (name "unconnected-(U2-VDDQ-PadG1)") (class "Default")
      (node (ref "U2") (pin "G1") (pinfunction "VDDQ_G1") (pintype "power_in"))
    )
    (net (code "260") (name "unconnected-(U2-VDDQ-PadG3)") (class "Default")
      (node (ref "U2") (pin "G3") (pinfunction "VDDQ_G3") (pintype "power_in"))
    )
    (net (code "261") (name "unconnected-(U2-VDDQ-PadG7)") (class "Default")
      (node (ref "U2") (pin "G7") (pinfunction "VDDQ_G7") (pintype "power_in"))
    )
    (net (code "262") (name "unconnected-(U2-VDDQ-PadG9)") (class "Default")
      (node (ref "U2") (pin "G9") (pinfunction "VDDQ_G9") (pintype "power_in"))
    )
    (net (code "263") (name "unconnected-(U2-VREF-PadJ2)") (class "Default")
      (node (ref "U2") (pin "J2") (pinfunction "VREF_J2") (pintype "power_in"))
    )
    (net (code "264") (name "unconnected-(U2-VSS-PadA3)") (class "Default")
      (node (ref "U2") (pin "A3") (pinfunction "VSS_A3") (pintype "power_in"))
    )
    (net (code "265") (name "unconnected-(U2-VSS-PadE3)") (class "Default")
      (node (ref "U2") (pin "E3") (pinfunction "VSS_E3") (pintype "power_in"))
    )
    (net (code "266") (name "unconnected-(U2-VSS-PadJ3)") (class "Default")
      (node (ref "U2") (pin "J3") (pinfunction "VSS_J3") (pintype "power_in"))
    )
    (net (code "267") (name "unconnected-(U2-VSS-PadN1)") (class "Default")
      (node (ref "U2") (pin "N1") (pinfunction "VSS_N1") (pintype "power_in"))
    )
    (net (code "268") (name "unconnected-(U2-VSS-PadP9)") (class "Default")
      (node (ref "U2") (pin "P9") (pinfunction "VSS_P9") (pintype "power_in"))
    )
    (net (code "269") (name "unconnected-(U2-VSSDL-PadJ7)") (class "Default")
      (node (ref "U2") (pin "J7") (pinfunction "VSSDL_J7") (pintype "power_in"))
    )
    (net (code "270") (name "unconnected-(U2-VSSQ-PadA7)") (class "Default")
      (node (ref "U2") (pin "A7") (pinfunction "VSSQ_A7") (pintype "power_in"))
    )
    (net (code "271") (name "unconnected-(U2-VSSQ-PadB2)") (class "Default")
      (node (ref "U2") (pin "B2") (pinfunction "VSSQ_B2") (pintype "power_in"))
    )
    (net (code "272") (name "unconnected-(U2-VSSQ-PadB8)") (class "Default")
      (node (ref "U2") (pin "B8") (pinfunction "VSSQ_B8") (pintype "power_in"))
    )
    (net (code "273") (name "unconnected-(U2-VSSQ-PadD2)") (class "Default")
      (node (ref "U2") (pin "D2") (pinfunction "VSSQ_D2") (pintype "power_in"))
    )
    (net (code "274") (name "unconnected-(U2-VSSQ-PadD8)") (class "Default")
      (node (ref "U2") (pin "D8") (pinfunction "VSSQ_D8") (pintype "power_in"))
    )
    (net (code "275") (name "unconnected-(U2-VSSQ-PadE7)") (class "Default")
      (node (ref "U2") (pin "E7") (pinfunction "VSSQ_E7") (pintype "power_in"))
    )
    (net (code "276") (name "unconnected-(U2-VSSQ-PadF2)") (class "Default")
      (node (ref "U2") (pin "F2") (pinfunction "VSSQ_F2") (pintype "power_in"))
    )
    (net (code "277") (name "unconnected-(U2-VSSQ-PadF8)") (class "Default")
      (node (ref "U2") (pin "F8") (pinfunction "VSSQ_F8") (pintype "power_in"))
    )
    (net (code "278") (name "unconnected-(U2-VSSQ-PadH2)") (class "Default")
      (node (ref "U2") (pin "H2") (pinfunction "VSSQ_H2") (pintype "power_in"))
    )
    (net (code "279") (name "unconnected-(U2-VSSQ-PadH8)") (class "Default")
      (node (ref "U2") (pin "H8") (pinfunction "VSSQ_H8") (pintype "power_in"))
    )
    (net (code "280") (name "unconnected-(U2-~{CAS}-PadL7)") (class "Default")
      (node (ref "U2") (pin "L7") (pinfunction "~{CAS}_L7") (pintype "bidirectional"))
    )
    (net (code "281") (name "unconnected-(U2-~{CK}-PadK8)") (class "Default")
      (node (ref "U2") (pin "K8") (pinfunction "~{CK}_K8") (pintype "bidirectional"))
    )
    (net (code "282") (name "unconnected-(U2-~{CS}-PadL8)") (class "Default")
      (node (ref "U2") (pin "L8") (pinfunction "~{CS}_L8") (pintype "bidirectional"))
    )
    (net (code "283") (name "unconnected-(U2-~{LDQS}-PadE8)") (class "Default")
      (node (ref "U2") (pin "E8") (pinfunction "~{LDQS}_E8") (pintype "bidirectional"))
    )
    (net (code "284") (name "unconnected-(U2-~{RAS}-PadK7)") (class "Default")
      (node (ref "U2") (pin "K7") (pinfunction "~{RAS}_K7") (pintype "bidirectional"))
    )
    (net (code "285") (name "unconnected-(U2-~{UDQS}-PadA8)") (class "Default")
      (node (ref "U2") (pin "A8") (pinfunction "~{UDQS}_A8") (pintype "bidirectional"))
    )
    (net (code "286") (name "unconnected-(U2-~{WE}-PadK3)") (class "Default")
      (node (ref "U2") (pin "K3") (pinfunction "~{WE}_K3") (pintype "bidirectional"))
    )
  )
)
